# SCH_m5_controller_2023-12-30.net
KiCad netlist of a schematic drawn in EasyEDA
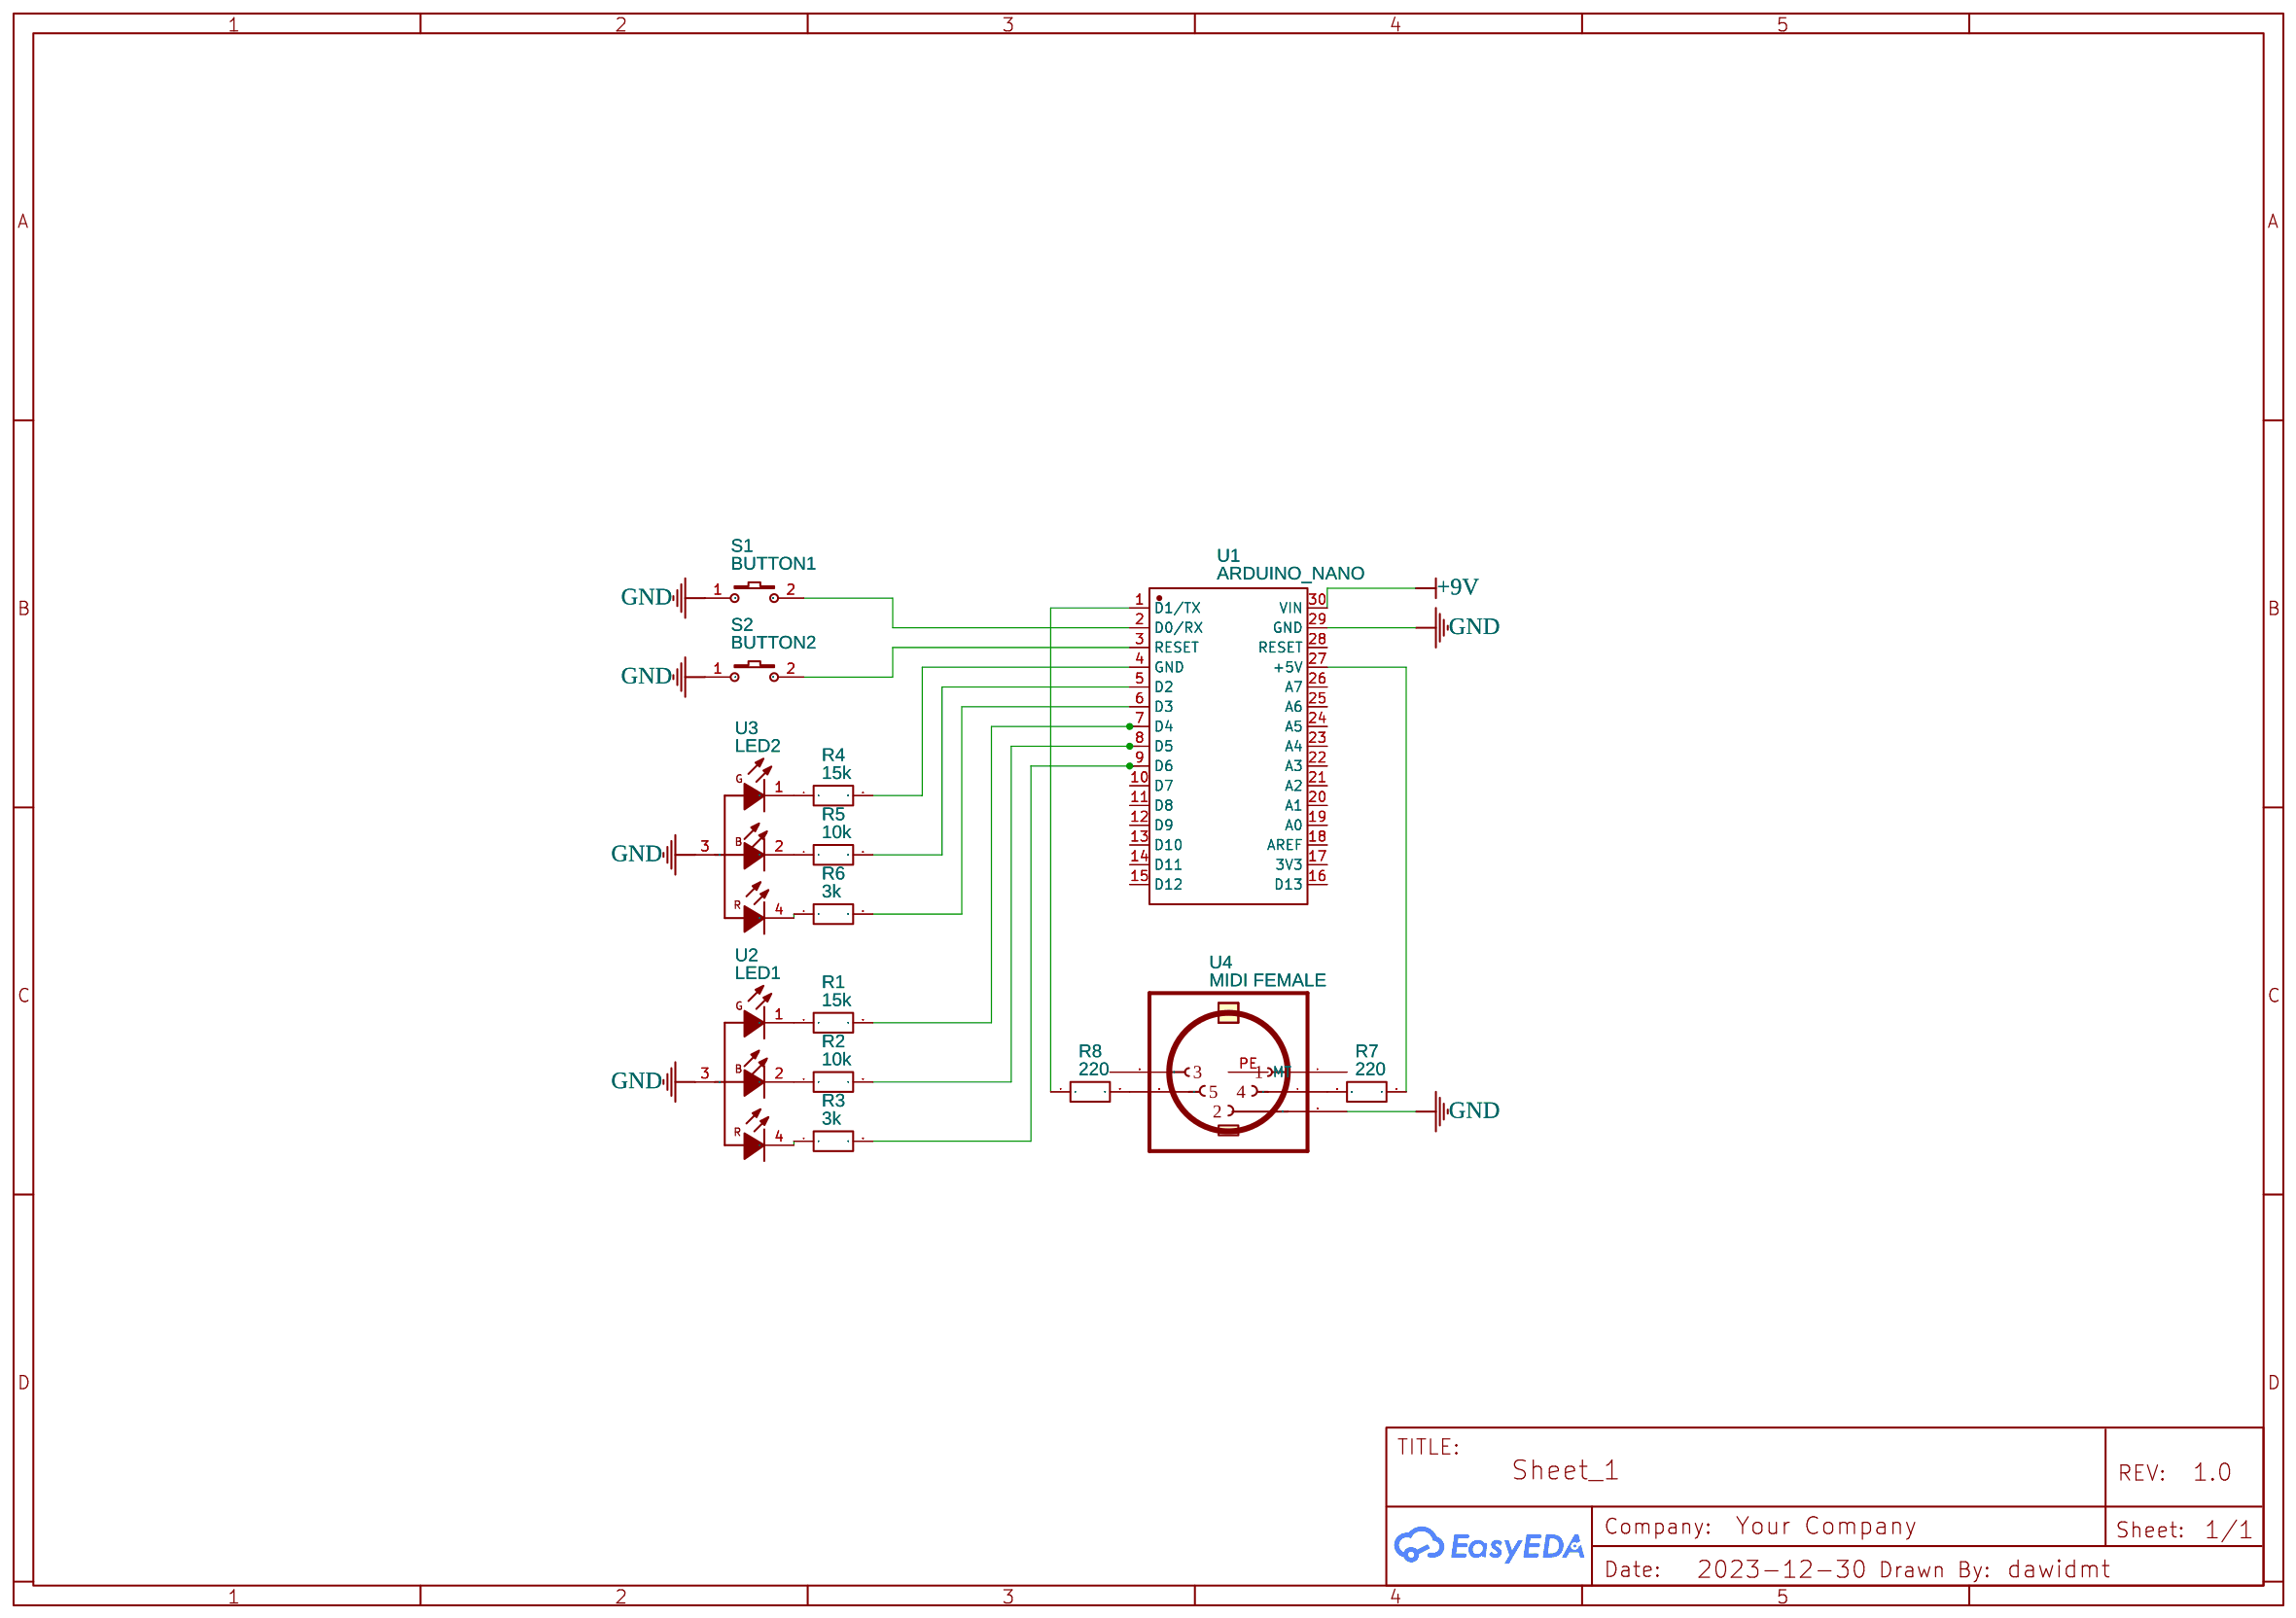
[diagram p0: schematic sheet]

(export (version "E")
  (design (tool "Eeschema 10.0.6"))
  (components
    (comp (ref "R1") (value "15k") (libsource (lib "") (part "R_0603_EU")))
    (comp (ref "R2") (value "10k") (libsource (lib "") (part "R_0603_EU")))
    (comp (ref "R3") (value "3k") (libsource (lib "") (part "R_0603_EU")))
    (comp (ref "R4") (value "15k") (libsource (lib "") (part "R_0603_EU")))
    (comp (ref "R5") (value "10k") (libsource (lib "") (part "R_0603_EU")))
    (comp (ref "R6") (value "3k") (libsource (lib "") (part "R_0603_EU")))
    (comp (ref "R7") (value "220") (libsource (lib "") (part "R_0603_EU_1")))
    (comp (ref "R8") (value "220") (libsource (lib "") (part "R_0603_EU")))
    (comp (ref "S1")
      (value "BUTTON1")
      (fields (field (name "Manufacturer Part") "K2-1107ST-A4SW-06"))
      (libsource (lib "") (part "K2-3.6×6.1_SMD"))
    )
    (comp (ref "S2")
      (value "BUTTON2")
      (fields (field (name "Manufacturer Part") "K2-1107ST-A4SW-06"))
      (libsource (lib "") (part "K2-3.6×6.1_SMD"))
    )
    (comp (ref "U1") (value "ARDUINO_NANO") (libsource (lib "") (part "ARDUINO_NANO")))
    (comp (ref "U2")
      (value "LED1")
      (fields (field (name "Manufacturer Part") "GT-3806URGBC"))
      (libsource (lib "") (part "GT-3806URGBC"))
    )
    (comp (ref "U3")
      (value "LED2")
      (fields (field (name "Manufacturer Part") "GT-3806URGBC"))
      (libsource (lib "") (part "GT-3806URGBC"))
    )
    (comp (ref "U4") (value "MIDI FEMALE") (libsource (lib "") (part "MIDIJACK")))
  )
  (nets
    (net (code "1") (name "+9V") (class "Default")
      (node (ref "U1") (pin "30") (pinfunction "VIN_30") (pintype "unspecified"))
    )
    (net (code "2") (name "GND") (class "Default")
      (node (ref "S1") (pin "1") (pinfunction "1_1") (pintype "unspecified"))
      (node (ref "S2") (pin "1") (pinfunction "1_1") (pintype "unspecified"))
      (node (ref "U1") (pin "29") (pinfunction "GND_29") (pintype "unspecified"))
      (node (ref "U2") (pin "3") (pinfunction "3_3") (pintype "unspecified"))
      (node (ref "U3") (pin "3") (pinfunction "3_3") (pintype "unspecified"))
      (node (ref "U4") (pin "2") (pinfunction "2_2") (pintype "unspecified"))
    )
    (net (code "3") (name "Net-(R1-Pad1)") (class "Default")
      (node (ref "R1") (pin "1") (pinfunction "1_1") (pintype "unspecified"))
      (node (ref "U2") (pin "1") (pinfunction "1_1") (pintype "unspecified"))
    )
    (net (code "4") (name "Net-(R2-Pad1)") (class "Default")
      (node (ref "R2") (pin "1") (pinfunction "1_1") (pintype "unspecified"))
      (node (ref "U2") (pin "2") (pinfunction "1_2") (pintype "unspecified"))
    )
    (net (code "5") (name "Net-(R3-Pad1)") (class "Default")
      (node (ref "R3") (pin "1") (pinfunction "1_1") (pintype "unspecified"))
      (node (ref "U2") (pin "4") (pinfunction "4_4") (pintype "unspecified"))
    )
    (net (code "6") (name "Net-(R4-Pad1)") (class "Default")
      (node (ref "R4") (pin "1") (pinfunction "1_1") (pintype "unspecified"))
      (node (ref "U3") (pin "1") (pinfunction "1_1") (pintype "unspecified"))
    )
    (net (code "7") (name "Net-(R4-Pad2)") (class "Default")
      (node (ref "R4") (pin "2") (pinfunction "2_2") (pintype "unspecified"))
      (node (ref "U1") (pin "4") (pinfunction "GND_4") (pintype "unspecified"))
    )
    (net (code "8") (name "Net-(R5-Pad1)") (class "Default")
      (node (ref "R5") (pin "1") (pinfunction "1_1") (pintype "unspecified"))
      (node (ref "U3") (pin "2") (pinfunction "1_2") (pintype "unspecified"))
    )
    (net (code "9") (name "Net-(R6-Pad1)") (class "Default")
      (node (ref "R6") (pin "1") (pinfunction "1_1") (pintype "unspecified"))
      (node (ref "U3") (pin "4") (pinfunction "4_4") (pintype "unspecified"))
    )
    (net (code "10") (name "Net-(R7-Pad2)") (class "Default")
      (node (ref "R7") (pin "2") (pinfunction "2_2") (pintype "unspecified"))
      (node (ref "U4") (pin "4") (pinfunction "4_4") (pintype "unspecified"))
    )
    (net (code "11") (name "Net-(R8-Pad2)") (class "Default")
      (node (ref "R8") (pin "2") (pinfunction "2_2") (pintype "unspecified"))
      (node (ref "U4") (pin "5") (pinfunction "5_5") (pintype "unspecified"))
    )
    (net (code "12") (name "Net-(S2-Pad2)") (class "Default")
      (node (ref "S2") (pin "2") (pinfunction "2_2") (pintype "unspecified"))
      (node (ref "U1") (pin "3") (pinfunction "RESET_3") (pintype "unspecified"))
    )
    (net (code "13") (name "Net-(U1-+5V)") (class "Default")
      (node (ref "R7") (pin "1") (pinfunction "1_1") (pintype "unspecified"))
      (node (ref "U1") (pin "27") (pinfunction "+5V_27") (pintype "unspecified"))
    )
    (net (code "14") (name "Net-(U1-D0{slash}RX)") (class "Default")
      (node (ref "S1") (pin "2") (pinfunction "2_2") (pintype "unspecified"))
      (node (ref "U1") (pin "2") (pinfunction "D0/RX_2") (pintype "unspecified"))
    )
    (net (code "15") (name "Net-(U1-D1{slash}TX)") (class "Default")
      (node (ref "R8") (pin "1") (pinfunction "1_1") (pintype "unspecified"))
      (node (ref "U1") (pin "1") (pinfunction "D1/TX_1") (pintype "unspecified"))
    )
    (net (code "16") (name "Net-(U1-D2)") (class "Default")
      (node (ref "R5") (pin "2") (pinfunction "2_2") (pintype "unspecified"))
      (node (ref "U1") (pin "5") (pinfunction "D2_5") (pintype "unspecified"))
    )
    (net (code "17") (name "Net-(U1-D3)") (class "Default")
      (node (ref "R6") (pin "2") (pinfunction "2_2") (pintype "unspecified"))
      (node (ref "U1") (pin "6") (pinfunction "D3_6") (pintype "unspecified"))
    )
    (net (code "18") (name "Net-(U1-D4)") (class "Default")
      (node (ref "R1") (pin "2") (pinfunction "2_2") (pintype "unspecified"))
      (node (ref "U1") (pin "7") (pinfunction "D4_7") (pintype "unspecified"))
    )
    (net (code "19") (name "Net-(U1-D5)") (class "Default")
      (node (ref "R2") (pin "2") (pinfunction "2_2") (pintype "unspecified"))
      (node (ref "U1") (pin "8") (pinfunction "D5_8") (pintype "unspecified"))
    )
    (net (code "20") (name "Net-(U1-D6)") (class "Default")
      (node (ref "R3") (pin "2") (pinfunction "2_2") (pintype "unspecified"))
      (node (ref "U1") (pin "9") (pinfunction "D6_9") (pintype "unspecified"))
    )
    (net (code "21") (name "unconnected-(U1-3V3-Pad17)") (class "Default")
      (node (ref "U1") (pin "17") (pinfunction "3V3_17") (pintype "unspecified"))
    )
    (net (code "22") (name "unconnected-(U1-A0-Pad19)") (class "Default")
      (node (ref "U1") (pin "19") (pinfunction "A0_19") (pintype "unspecified"))
    )
    (net (code "23") (name "unconnected-(U1-A1-Pad20)") (class "Default")
      (node (ref "U1") (pin "20") (pinfunction "A1_20") (pintype "unspecified"))
    )
    (net (code "24") (name "unconnected-(U1-A2-Pad21)") (class "Default")
      (node (ref "U1") (pin "21") (pinfunction "A2_21") (pintype "unspecified"))
    )
    (net (code "25") (name "unconnected-(U1-A3-Pad22)") (class "Default")
      (node (ref "U1") (pin "22") (pinfunction "A3_22") (pintype "unspecified"))
    )
    (net (code "26") (name "unconnected-(U1-A4-Pad23)") (class "Default")
      (node (ref "U1") (pin "23") (pinfunction "A4_23") (pintype "unspecified"))
    )
    (net (code "27") (name "unconnected-(U1-A5-Pad24)") (class "Default")
      (node (ref "U1") (pin "24") (pinfunction "A5_24") (pintype "unspecified"))
    )
    (net (code "28") (name "unconnected-(U1-A6-Pad25)") (class "Default")
      (node (ref "U1") (pin "25") (pinfunction "A6_25") (pintype "unspecified"))
    )
    (net (code "29") (name "unconnected-(U1-A7-Pad26)") (class "Default")
      (node (ref "U1") (pin "26") (pinfunction "A7_26") (pintype "unspecified"))
    )
    (net (code "30") (name "unconnected-(U1-AREF-Pad18)") (class "Default")
      (node (ref "U1") (pin "18") (pinfunction "AREF_18") (pintype "unspecified"))
    )
    (net (code "31") (name "unconnected-(U1-D7-Pad10)") (class "Default")
      (node (ref "U1") (pin "10") (pinfunction "D7_10") (pintype "unspecified"))
    )
    (net (code "32") (name "unconnected-(U1-D8-Pad11)") (class "Default")
      (node (ref "U1") (pin "11") (pinfunction "D8_11") (pintype "unspecified"))
    )
    (net (code "33") (name "unconnected-(U1-D9-Pad12)") (class "Default")
      (node (ref "U1") (pin "12") (pinfunction "D9_12") (pintype "unspecified"))
    )
    (net (code "34") (name "unconnected-(U1-D10-Pad13)") (class "Default")
      (node (ref "U1") (pin "13") (pinfunction "D10_13") (pintype "unspecified"))
    )
    (net (code "35") (name "unconnected-(U1-D11-Pad14)") (class "Default")
      (node (ref "U1") (pin "14") (pinfunction "D11_14") (pintype "unspecified"))
    )
    (net (code "36") (name "unconnected-(U1-D12-Pad15)") (class "Default")
      (node (ref "U1") (pin "15") (pinfunction "D12_15") (pintype "unspecified"))
    )
    (net (code "37") (name "unconnected-(U1-D13-Pad16)") (class "Default")
      (node (ref "U1") (pin "16") (pinfunction "D13_16") (pintype "unspecified"))
    )
    (net (code "38") (name "unconnected-(U1-RESET-Pad28)") (class "Default")
      (node (ref "U1") (pin "28") (pinfunction "RESET_28") (pintype "unspecified"))
    )
    (net (code "39") (name "unconnected-(U4-MT-PadPE)") (class "Default")
      (node (ref "U4") (pin "PE") (pinfunction "MT_PE") (pintype "unspecified"))
    )
    (net (code "40") (name "unconnected-(U4-Pad1)") (class "Default")
      (node (ref "U4") (pin "1") (pinfunction "1_1") (pintype "unspecified"))
    )
    (net (code "41") (name "unconnected-(U4-Pad3)") (class "Default")
      (node (ref "U4") (pin "3") (pinfunction "3_3") (pintype "unspecified"))
    )
  )
)
